# orp_adc_iso.net
KiCad netlist of a schematic drawn in EAGLE
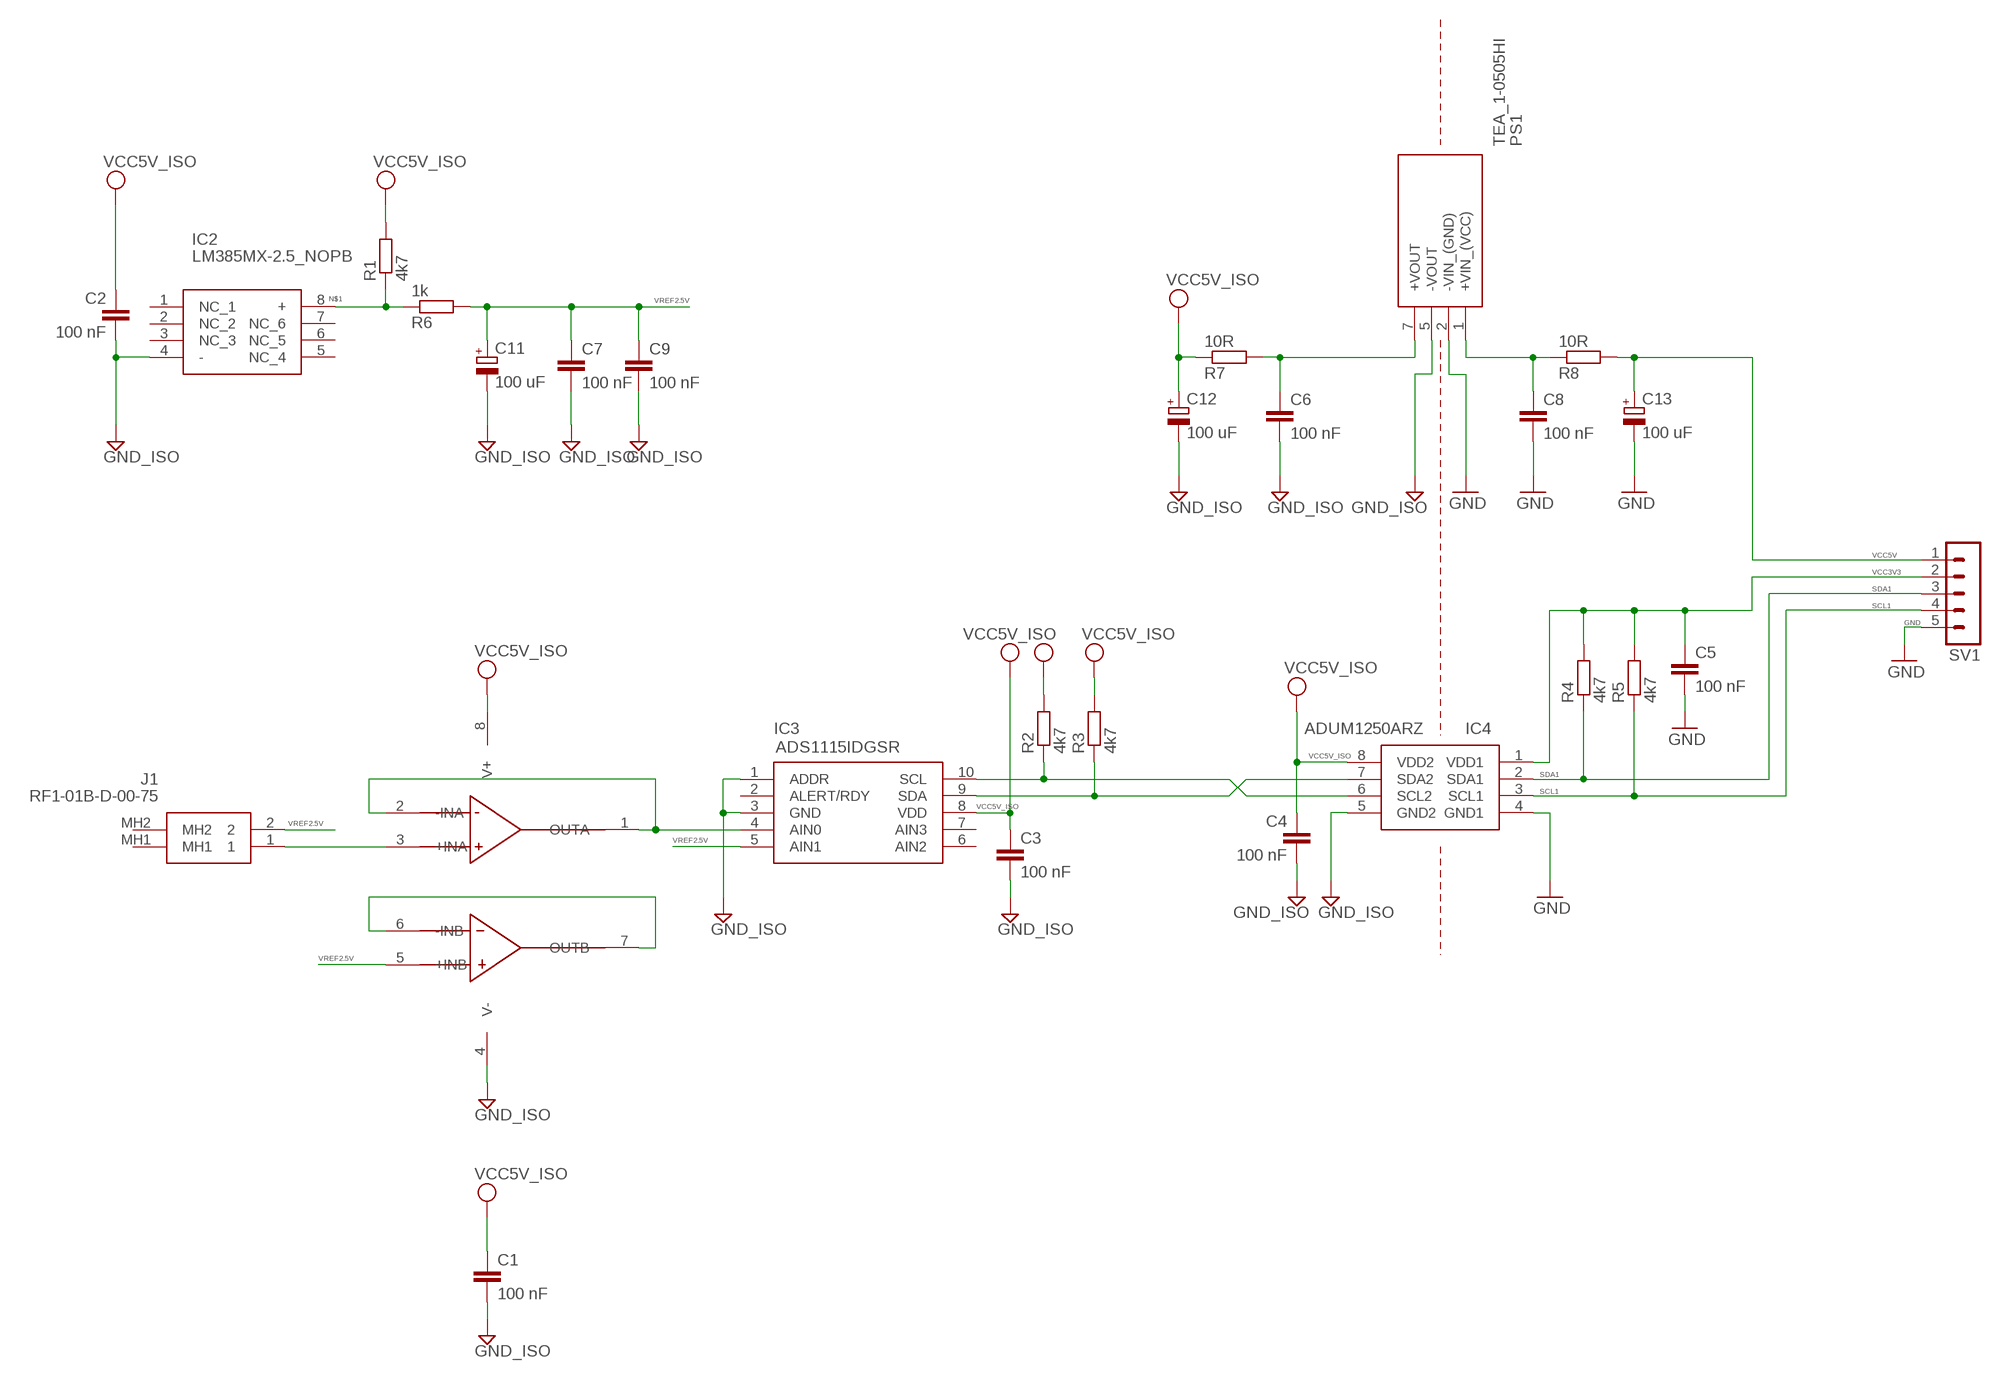
[diagram p0: schematic, sheet 1]

(export (version "E")
  (design (tool "Eeschema 10.0.6"))
  (components
    (comp (ref "C1")
      (value "100 nF")
      (footprint "eagle-import:C0603")
      (libsource (lib "eagle-import") (part "C-EUC0603"))
    )
    (comp (ref "C2")
      (value "100 nF")
      (footprint "eagle-import:C0603")
      (libsource (lib "eagle-import") (part "C-EUC0603"))
    )
    (comp (ref "C3")
      (value "100 nF")
      (footprint "eagle-import:C0603")
      (libsource (lib "eagle-import") (part "C-EUC0603"))
    )
    (comp (ref "C4")
      (value "100 nF")
      (footprint "eagle-import:C0603")
      (libsource (lib "eagle-import") (part "C-EUC0603"))
    )
    (comp (ref "C5")
      (value "100 nF")
      (footprint "eagle-import:C0603")
      (libsource (lib "eagle-import") (part "C-EUC0603"))
    )
    (comp (ref "C6")
      (value "100 nF")
      (footprint "eagle-import:C0603")
      (libsource (lib "eagle-import") (part "C-EUC0603"))
    )
    (comp (ref "C7")
      (value "100 nF")
      (footprint "eagle-import:C0603")
      (libsource (lib "eagle-import") (part "C-EUC0603"))
    )
    (comp (ref "C8")
      (value "100 nF")
      (footprint "eagle-import:C0603")
      (libsource (lib "eagle-import") (part "C-EUC0603"))
    )
    (comp (ref "C9")
      (value "100 nF")
      (footprint "eagle-import:C0603")
      (libsource (lib "eagle-import") (part "C-EUC0603"))
    )
    (comp (ref "C11")
      (value "100 uF")
      (footprint "eagle-import:SMC_C")
      (libsource (lib "eagle-import") (part "CPOL-EUSMCC"))
    )
    (comp (ref "C12")
      (value "100 uF")
      (footprint "eagle-import:SMC_C")
      (libsource (lib "eagle-import") (part "CPOL-EUSMCC"))
    )
    (comp (ref "C13")
      (value "100 uF")
      (footprint "eagle-import:SMC_C")
      (libsource (lib "eagle-import") (part "CPOL-EUSMCC"))
    )
    (comp (ref "IC2")
      (value "LM385MX-2.5_NOPB")
      (footprint "eagle-import:SOIC127P600X175-8N")
      (fields (field (name "MANUFACTURER_PART_NUMBER") "LM385MX-2.5/NOPB"))
      (libsource (lib "eagle-import") (part "LM385MX-2.5_NOPB"))
    )
    (comp (ref "IC3")
      (value "ADS1115IDGSR")
      (footprint "eagle-import:SOP50P490X110-10N")
      (libsource (lib "eagle-import") (part "ADS1115IDGSR"))
    )
    (comp (ref "IC4")
      (value "ADUM1250ARZ")
      (footprint "eagle-import:SOIC127P600X175-8N")
      (libsource (lib "eagle-import") (part "ADUM1250ARZ"))
    )
    (comp (ref "J1")
      (value "RF1-01B-D-00-75")
      (footprint "eagle-import:RF101BD0075")
      (libsource (lib "eagle-import") (part "RF1-01B-D-00-75"))
    )
    (comp (ref "PS1")
      (value "TEA_1-0505HI")
      (footprint "eagle-import:TEA10505HI")
      (fields (field (name "MANUFACTURER_PART_NUMBER") "TEA 1-0505HI"))
      (libsource (lib "eagle-import") (part "TEA_1-0505HI"))
    )
    (comp (ref "R1")
      (value "4k7")
      (footprint "eagle-import:R0603")
      (libsource (lib "eagle-import") (part "R-EU_R0603"))
    )
    (comp (ref "R2")
      (value "4k7")
      (footprint "eagle-import:R0603")
      (libsource (lib "eagle-import") (part "R-EU_R0603"))
    )
    (comp (ref "R3")
      (value "4k7")
      (footprint "eagle-import:R0603")
      (libsource (lib "eagle-import") (part "R-EU_R0603"))
    )
    (comp (ref "R4")
      (value "4k7")
      (footprint "eagle-import:R0603")
      (libsource (lib "eagle-import") (part "R-EU_R0603"))
    )
    (comp (ref "R5")
      (value "4k7")
      (footprint "eagle-import:R0603")
      (libsource (lib "eagle-import") (part "R-EU_R0603"))
    )
    (comp (ref "R6")
      (value "1k")
      (footprint "eagle-import:R0603")
      (libsource (lib "eagle-import") (part "R-EU_R0603"))
    )
    (comp (ref "R7")
      (value "10R")
      (footprint "eagle-import:R0603")
      (libsource (lib "eagle-import") (part "R-EU_R0603"))
    )
    (comp (ref "R8")
      (value "10R")
      (footprint "eagle-import:R0603")
      (libsource (lib "eagle-import") (part "R-EU_R0603"))
    )
    (comp (ref "SV1")
      (value "MA05-1")
      (footprint "eagle-import:MA05-1")
      (libsource (lib "eagle-import") (part "MA05-1"))
    )
    (comp (ref "U$1")
      (value "LMC6482AIMX/NOPB")
      (footprint "eagle-import:SO8")
      (libsource (lib "eagle-import") (part "LMC6482AIMX/NOPB"))
    )
  )
  (nets
    (net (code "1") (name "/N$1") (class "Default")
      (node (ref "IC2") (pin "8") (pinfunction "+_8") (pintype "bidirectional"))
      (node (ref "R1") (pin "1") (pinfunction "1_1") (pintype "passive"))
      (node (ref "R6") (pin "1") (pinfunction "1_1") (pintype "passive"))
    )
    (net (code "2") (name "/SCL1") (class "Default")
      (node (ref "IC4") (pin "3") (pinfunction "SCL1_3") (pintype "bidirectional"))
      (node (ref "R5") (pin "1") (pinfunction "1_1") (pintype "passive"))
      (node (ref "SV1") (pin "4") (pinfunction "4_4") (pintype "passive"))
    )
    (net (code "3") (name "/SDA1") (class "Default")
      (node (ref "IC4") (pin "2") (pinfunction "SDA1_2") (pintype "bidirectional"))
      (node (ref "R4") (pin "1") (pinfunction "1_1") (pintype "passive"))
      (node (ref "SV1") (pin "3") (pinfunction "3_3") (pintype "passive"))
    )
    (net (code "4") (name "/VCC3V3") (class "Default")
      (node (ref "C5") (pin "1") (pinfunction "1_1") (pintype "passive"))
      (node (ref "IC4") (pin "1") (pinfunction "VDD1_1") (pintype "bidirectional"))
      (node (ref "R4") (pin "2") (pinfunction "2_2") (pintype "passive"))
      (node (ref "R5") (pin "2") (pinfunction "2_2") (pintype "passive"))
      (node (ref "SV1") (pin "2") (pinfunction "2_2") (pintype "passive"))
    )
    (net (code "5") (name "/VCC5V") (class "Default")
      (node (ref "C13") (pin "+") (pinfunction "+_+") (pintype "passive"))
      (node (ref "R8") (pin "2") (pinfunction "2_2") (pintype "passive"))
      (node (ref "SV1") (pin "1") (pinfunction "1_1") (pintype "passive"))
    )
    (net (code "6") (name "/VREF2.5V") (class "Default")
      (node (ref "C11") (pin "+") (pinfunction "+_+") (pintype "passive"))
      (node (ref "C7") (pin "1") (pinfunction "1_1") (pintype "passive"))
      (node (ref "C9") (pin "1") (pinfunction "1_1") (pintype "passive"))
      (node (ref "IC3") (pin "5") (pinfunction "AIN1_5") (pintype "bidirectional"))
      (node (ref "J1") (pin "2") (pinfunction "2_2") (pintype "bidirectional"))
      (node (ref "R6") (pin "2") (pinfunction "2_2") (pintype "passive"))
      (node (ref "U$1") (pin "5") (pinfunction "+INB_5") (pintype "bidirectional"))
    )
    (net (code "7") (name "GND") (class "Default")
      (node (ref "C13") (pin "-") (pinfunction "-_-") (pintype "passive"))
      (node (ref "C5") (pin "2") (pinfunction "2_2") (pintype "passive"))
      (node (ref "C8") (pin "2") (pinfunction "2_2") (pintype "passive"))
      (node (ref "IC4") (pin "4") (pinfunction "GND1_4") (pintype "bidirectional"))
      (node (ref "PS1") (pin "2") (pinfunction "-VIN_(GND)_2") (pintype "bidirectional"))
      (node (ref "SV1") (pin "5") (pinfunction "5_5") (pintype "passive"))
    )
    (net (code "8") (name "GND_ISO") (class "Default")
      (node (ref "C1") (pin "2") (pinfunction "2_2") (pintype "passive"))
      (node (ref "C11") (pin "-") (pinfunction "-_-") (pintype "passive"))
      (node (ref "C12") (pin "-") (pinfunction "-_-") (pintype "passive"))
      (node (ref "C2") (pin "2") (pinfunction "2_2") (pintype "passive"))
      (node (ref "C3") (pin "2") (pinfunction "2_2") (pintype "passive"))
      (node (ref "C4") (pin "2") (pinfunction "2_2") (pintype "passive"))
      (node (ref "C6") (pin "2") (pinfunction "2_2") (pintype "passive"))
      (node (ref "C7") (pin "2") (pinfunction "2_2") (pintype "passive"))
      (node (ref "C9") (pin "2") (pinfunction "2_2") (pintype "passive"))
      (node (ref "IC2") (pin "4") (pinfunction "-_4") (pintype "bidirectional"))
      (node (ref "IC3") (pin "1") (pinfunction "ADDR_1") (pintype "bidirectional"))
      (node (ref "IC3") (pin "3") (pinfunction "GND_3") (pintype "bidirectional"))
      (node (ref "IC4") (pin "5") (pinfunction "GND2_5") (pintype "bidirectional"))
      (node (ref "PS1") (pin "5") (pinfunction "-VOUT_5") (pintype "bidirectional"))
      (node (ref "U$1") (pin "4") (pinfunction "V-_4") (pintype "bidirectional"))
    )
    (net (code "9") (name "Net-(IC3-AIN0)") (class "Default")
      (node (ref "IC3") (pin "4") (pinfunction "AIN0_4") (pintype "bidirectional"))
      (node (ref "U$1") (pin "1") (pinfunction "OUTA_1") (pintype "bidirectional"))
      (node (ref "U$1") (pin "2") (pinfunction "-INA_2") (pintype "bidirectional"))
    )
    (net (code "10") (name "Net-(IC3-SCL)") (class "Default")
      (node (ref "IC3") (pin "10") (pinfunction "SCL_10") (pintype "bidirectional"))
      (node (ref "IC4") (pin "6") (pinfunction "SCL2_6") (pintype "bidirectional"))
      (node (ref "R2") (pin "1") (pinfunction "1_1") (pintype "passive"))
    )
    (net (code "11") (name "Net-(IC3-SDA)") (class "Default")
      (node (ref "IC3") (pin "9") (pinfunction "SDA_9") (pintype "bidirectional"))
      (node (ref "IC4") (pin "7") (pinfunction "SDA2_7") (pintype "bidirectional"))
      (node (ref "R3") (pin "1") (pinfunction "1_1") (pintype "passive"))
    )
    (net (code "12") (name "Net-(PS1-+VIN_(VCC))") (class "Default")
      (node (ref "C8") (pin "1") (pinfunction "1_1") (pintype "passive"))
      (node (ref "PS1") (pin "1") (pinfunction "+VIN_(VCC)_1") (pintype "bidirectional"))
      (node (ref "R8") (pin "1") (pinfunction "1_1") (pintype "passive"))
    )
    (net (code "13") (name "Net-(PS1-+VOUT)") (class "Default")
      (node (ref "C6") (pin "1") (pinfunction "1_1") (pintype "passive"))
      (node (ref "PS1") (pin "7") (pinfunction "+VOUT_7") (pintype "bidirectional"))
      (node (ref "R7") (pin "2") (pinfunction "2_2") (pintype "passive"))
    )
    (net (code "14") (name "Net-(U$1-+INA)") (class "Default")
      (node (ref "J1") (pin "1") (pinfunction "1_1") (pintype "bidirectional"))
      (node (ref "U$1") (pin "3") (pinfunction "+INA_3") (pintype "bidirectional"))
    )
    (net (code "15") (name "Net-(U$1--INB)") (class "Default")
      (node (ref "U$1") (pin "6") (pinfunction "-INB_6") (pintype "bidirectional"))
      (node (ref "U$1") (pin "7") (pinfunction "OUTB_7") (pintype "bidirectional"))
    )
    (net (code "16") (name "VCC5V_ISO") (class "Default")
      (node (ref "C1") (pin "1") (pinfunction "1_1") (pintype "passive"))
      (node (ref "C12") (pin "+") (pinfunction "+_+") (pintype "passive"))
      (node (ref "C2") (pin "1") (pinfunction "1_1") (pintype "passive"))
      (node (ref "C3") (pin "1") (pinfunction "1_1") (pintype "passive"))
      (node (ref "C4") (pin "1") (pinfunction "1_1") (pintype "passive"))
      (node (ref "IC3") (pin "8") (pinfunction "VDD_8") (pintype "bidirectional"))
      (node (ref "IC4") (pin "8") (pinfunction "VDD2_8") (pintype "bidirectional"))
      (node (ref "R1") (pin "2") (pinfunction "2_2") (pintype "passive"))
      (node (ref "R2") (pin "2") (pinfunction "2_2") (pintype "passive"))
      (node (ref "R3") (pin "2") (pinfunction "2_2") (pintype "passive"))
      (node (ref "R7") (pin "1") (pinfunction "1_1") (pintype "passive"))
      (node (ref "U$1") (pin "8") (pinfunction "V+_8") (pintype "bidirectional"))
    )
    (net (code "17") (name "unconnected-(IC2-NC_1-Pad1)") (class "Default")
      (node (ref "IC2") (pin "1") (pinfunction "NC_1_1") (pintype "bidirectional"))
    )
    (net (code "18") (name "unconnected-(IC2-NC_2-Pad2)") (class "Default")
      (node (ref "IC2") (pin "2") (pinfunction "NC_2_2") (pintype "bidirectional"))
    )
    (net (code "19") (name "unconnected-(IC2-NC_3-Pad3)") (class "Default")
      (node (ref "IC2") (pin "3") (pinfunction "NC_3_3") (pintype "bidirectional"))
    )
    (net (code "20") (name "unconnected-(IC2-NC_4-Pad5)") (class "Default")
      (node (ref "IC2") (pin "5") (pinfunction "NC_4_5") (pintype "bidirectional"))
    )
    (net (code "21") (name "unconnected-(IC2-NC_5-Pad6)") (class "Default")
      (node (ref "IC2") (pin "6") (pinfunction "NC_5_6") (pintype "bidirectional"))
    )
    (net (code "22") (name "unconnected-(IC2-NC_6-Pad7)") (class "Default")
      (node (ref "IC2") (pin "7") (pinfunction "NC_6_7") (pintype "bidirectional"))
    )
    (net (code "23") (name "unconnected-(IC3-AIN2-Pad6)") (class "Default")
      (node (ref "IC3") (pin "6") (pinfunction "AIN2_6") (pintype "bidirectional"))
    )
    (net (code "24") (name "unconnected-(IC3-AIN3-Pad7)") (class "Default")
      (node (ref "IC3") (pin "7") (pinfunction "AIN3_7") (pintype "bidirectional"))
    )
    (net (code "25") (name "unconnected-(IC3-ALERT{slash}RDY-Pad2)") (class "Default")
      (node (ref "IC3") (pin "2") (pinfunction "ALERT/RDY_2") (pintype "bidirectional"))
    )
    (net (code "26") (name "unconnected-(J1-PadMH1)") (class "Default")
      (node (ref "J1") (pin "MH1") (pinfunction "MH1_MH1") (pintype "bidirectional"))
    )
    (net (code "27") (name "unconnected-(J1-PadMH2)") (class "Default")
      (node (ref "J1") (pin "MH2") (pinfunction "MH2_MH2") (pintype "bidirectional"))
    )
  )
)
